# BBB_Headers.net
KiCad netlist of a schematic drawn in Altium Designer
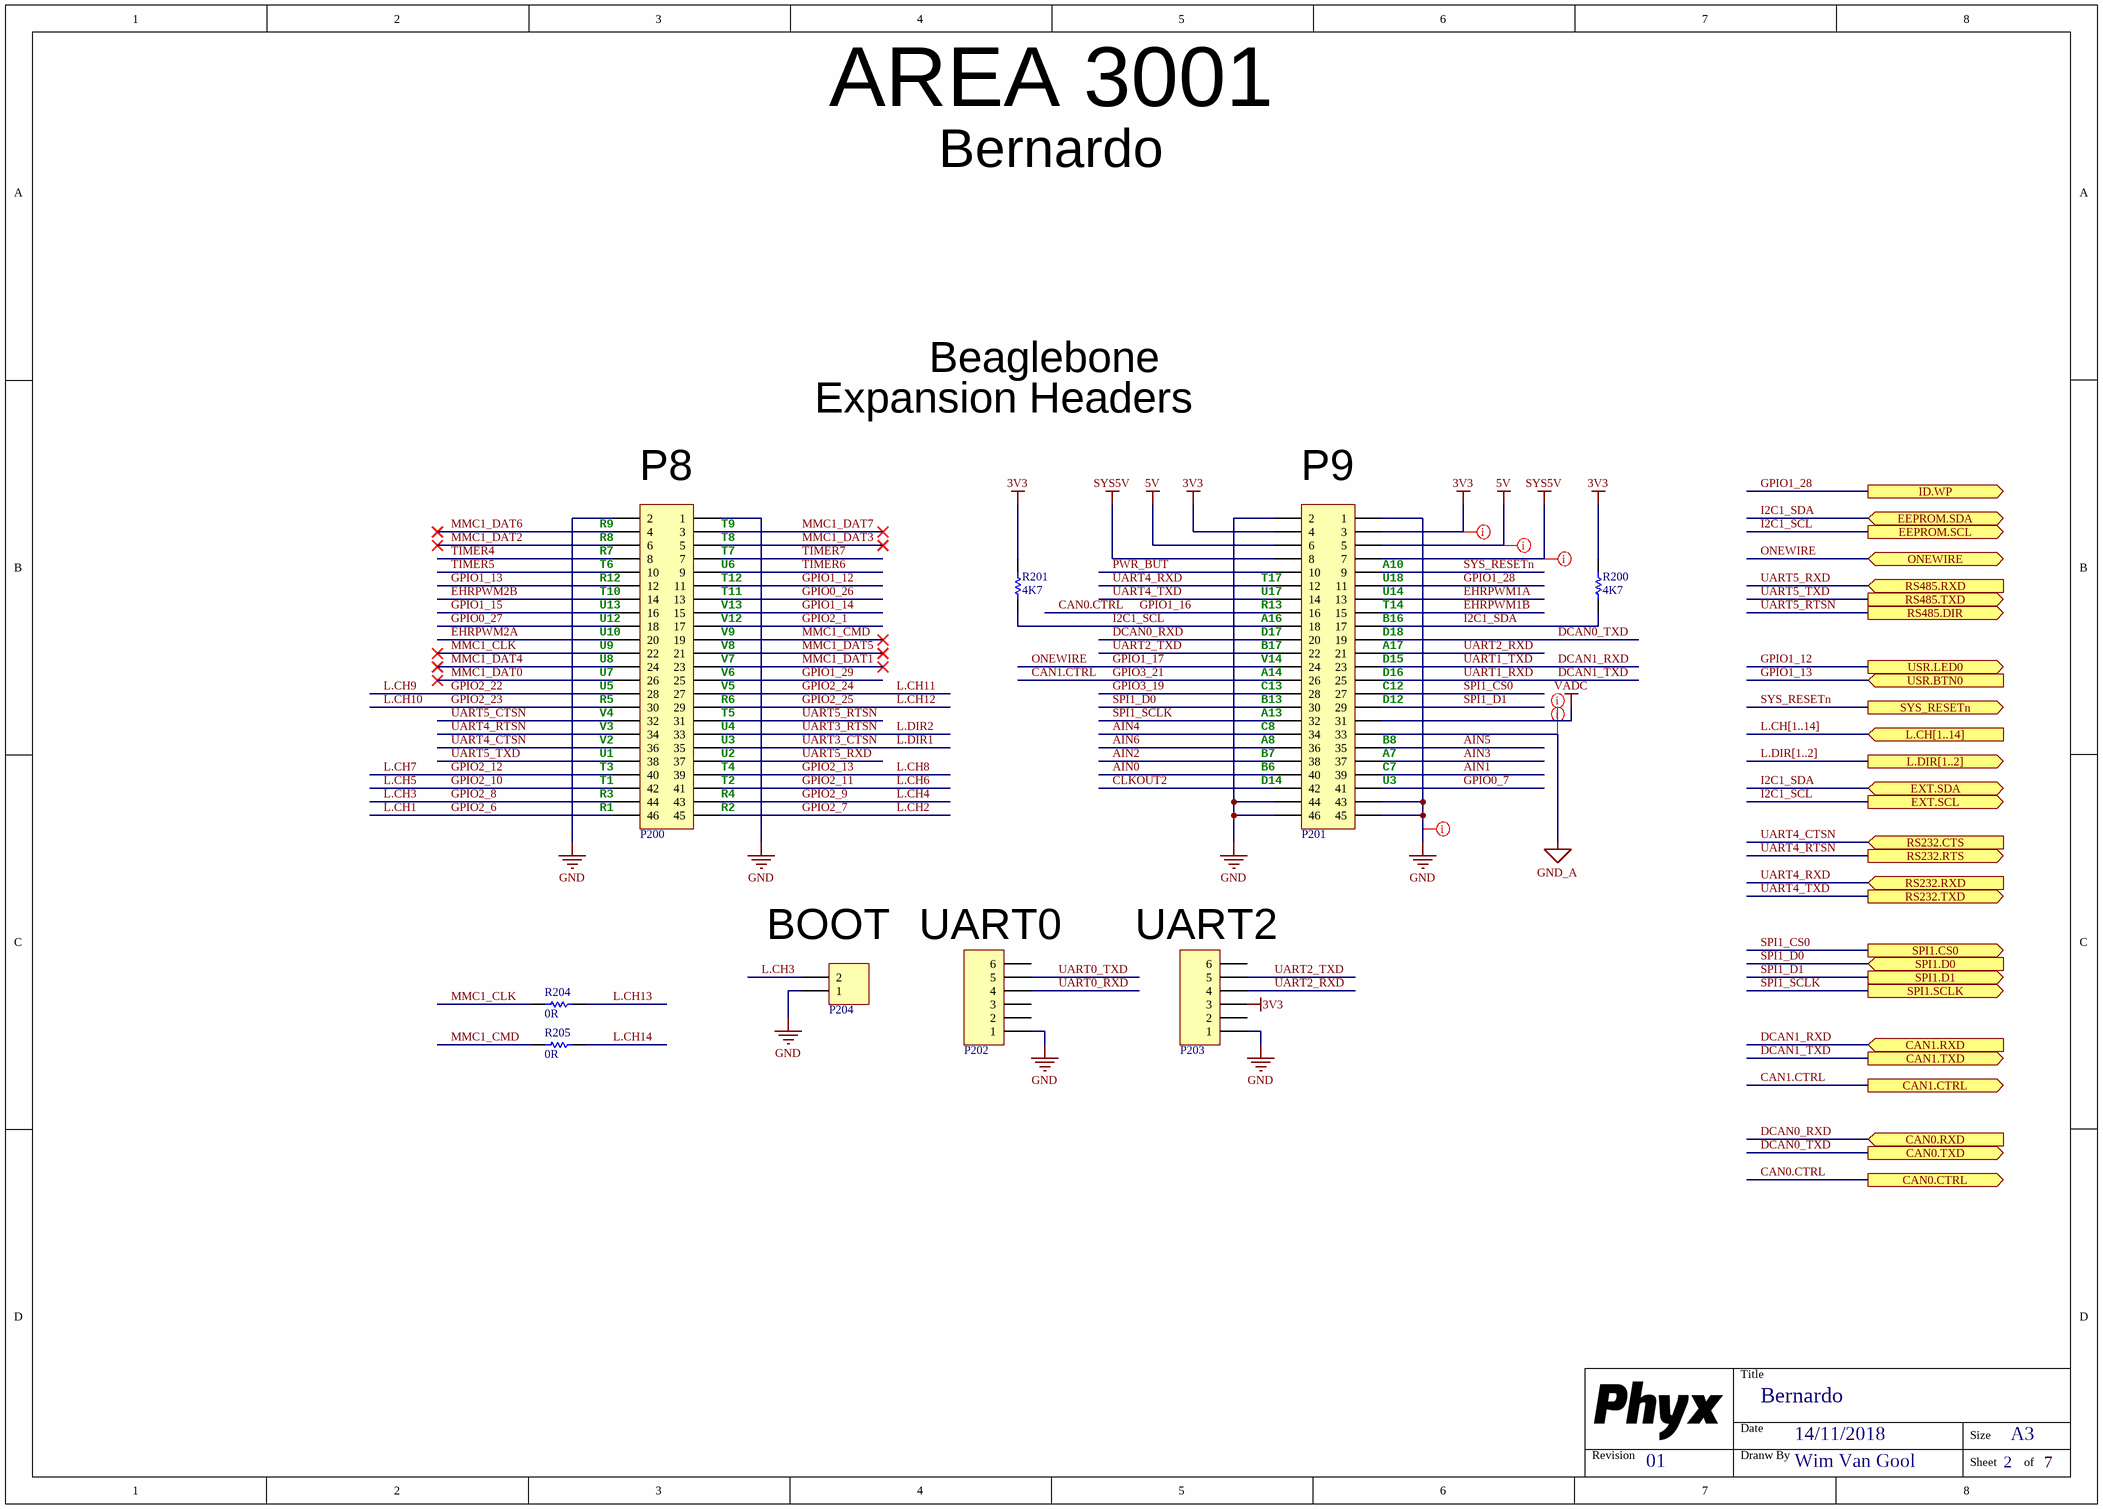
[diagram p0: BBB_Headers.SchDoc]

(export (version "E")
  (design (tool "Eeschema 10.0.6"))
  (components
    (comp (ref "P200")
      (value "Receptacle 23X2")
      (footprint "HDR2X23")
      (description "=Description")
      (libsource (lib "Phyx_Components") (part "Header 23X2"))
    )
    (comp (ref "P201")
      (value "Receptacle 23X2")
      (footprint "HDR2X23")
      (description "=Description")
      (libsource (lib "Phyx_Components") (part "Header 23X2"))
    )
    (comp (ref "P202")
      (value "Receptacle 6")
      (footprint "RCPT1X6")
      (libsource (lib "Phyx_Components") (part "Header 6"))
    )
    (comp (ref "P203")
      (value "Header 6")
      (footprint "HDR1X6")
      (libsource (lib "Phyx_Components") (part "Header 6"))
    )
    (comp (ref "P204")
      (value "Header 2")
      (footprint "HDR1X2")
      (libsource (lib "Phyx_Components") (part "Header 2"))
    )
    (comp (ref "R200")
      (value "4K7")
      (footprint "R0603_N")
      (fields (field (name "Comment") "RESISTOR"))
      (libsource (lib "Phyx_Components") (part "RESISTOR"))
    )
    (comp (ref "R201")
      (value "4K7")
      (footprint "R0603_N")
      (fields (field (name "Comment") "RESISTOR"))
      (libsource (lib "Phyx_Components") (part "RESISTOR"))
    )
    (comp (ref "R204")
      (value "0R")
      (footprint "R0603_N")
      (fields (field (name "Comment") "RESISTOR"))
      (libsource (lib "Phyx_Components") (part "RESISTOR"))
    )
    (comp (ref "R205")
      (value "0R")
      (footprint "R0603_N")
      (fields (field (name "Comment") "RESISTOR"))
      (libsource (lib "Phyx_Components") (part "RESISTOR"))
    )
  )
  (nets
    (net (code "2") (name "/AIN0") (class "Default")
      (node (ref "P201") (pin "40") (pinfunction "40_40") (pintype "passive"))
    )
    (net (code "3") (name "/AIN1") (class "Default")
      (node (ref "P201") (pin "39") (pinfunction "39_39") (pintype "passive"))
    )
    (net (code "4") (name "/AIN2") (class "Default")
      (node (ref "P201") (pin "38") (pinfunction "38_38") (pintype "passive"))
    )
    (net (code "5") (name "/AIN3") (class "Default")
      (node (ref "P201") (pin "37") (pinfunction "37_37") (pintype "passive"))
    )
    (net (code "6") (name "/AIN4") (class "Default")
      (node (ref "P201") (pin "34") (pinfunction "34_34") (pintype "passive"))
    )
    (net (code "7") (name "/AIN5") (class "Default")
      (node (ref "P201") (pin "35") (pinfunction "35_35") (pintype "passive"))
    )
    (net (code "8") (name "/AIN6") (class "Default")
      (node (ref "P201") (pin "36") (pinfunction "36_36") (pintype "passive"))
    )
    (net (code "9") (name "/CAN0.CTRL") (class "Default")
      (node (ref "P201") (pin "16") (pinfunction "16_16") (pintype "passive"))
    )
    (net (code "10") (name "/CAN1.CTRL") (class "Default")
      (node (ref "P201") (pin "26") (pinfunction "26_26") (pintype "passive"))
    )
    (net (code "11") (name "/CLKOUT2") (class "Default")
      (node (ref "P201") (pin "42") (pinfunction "42_42") (pintype "passive"))
    )
    (net (code "12") (name "/DCAN0_RXD") (class "Default")
      (node (ref "P201") (pin "20") (pinfunction "20_20") (pintype "passive"))
    )
    (net (code "13") (name "/DCAN0_TXD") (class "Default")
      (node (ref "P201") (pin "19") (pinfunction "19_19") (pintype "passive"))
    )
    (net (code "14") (name "/DCAN1_RXD") (class "Default")
      (node (ref "P201") (pin "23") (pinfunction "23_23") (pintype "passive"))
    )
    (net (code "15") (name "/DCAN1_TXD") (class "Default")
      (node (ref "P201") (pin "25") (pinfunction "25_25") (pintype "passive"))
    )
    (net (code "16") (name "/EHRPWM1A") (class "Default")
      (node (ref "P201") (pin "13") (pinfunction "13_13") (pintype "passive"))
    )
    (net (code "17") (name "/EHRPWM1B") (class "Default")
      (node (ref "P201") (pin "15") (pinfunction "15_15") (pintype "passive"))
    )
    (net (code "18") (name "/EHRPWM2A") (class "Default")
      (node (ref "P200") (pin "20") (pinfunction "20_20") (pintype "passive"))
    )
    (net (code "19") (name "/EHRPWM2B") (class "Default")
      (node (ref "P200") (pin "14") (pinfunction "14_14") (pintype "passive"))
    )
    (net (code "20") (name "/GPIO0_7") (class "Default")
      (node (ref "P201") (pin "41") (pinfunction "41_41") (pintype "passive"))
    )
    (net (code "21") (name "/GPIO0_26") (class "Default")
      (node (ref "P200") (pin "13") (pinfunction "13_13") (pintype "passive"))
    )
    (net (code "22") (name "/GPIO0_27") (class "Default")
      (node (ref "P200") (pin "18") (pinfunction "18_18") (pintype "passive"))
    )
    (net (code "23") (name "/GPIO1_12") (class "Default")
      (node (ref "P200") (pin "11") (pinfunction "11_11") (pintype "passive"))
    )
    (net (code "24") (name "/GPIO1_13") (class "Default")
      (node (ref "P200") (pin "12") (pinfunction "12_12") (pintype "passive"))
    )
    (net (code "25") (name "/GPIO1_14") (class "Default")
      (node (ref "P200") (pin "15") (pinfunction "15_15") (pintype "passive"))
    )
    (net (code "26") (name "/GPIO1_15") (class "Default")
      (node (ref "P200") (pin "16") (pinfunction "16_16") (pintype "passive"))
    )
    (net (code "27") (name "/GPIO1_17") (class "Default")
      (node (ref "P201") (pin "24") (pinfunction "24_24") (pintype "passive"))
    )
    (net (code "28") (name "/GPIO1_28") (class "Default")
      (node (ref "P201") (pin "11") (pinfunction "11_11") (pintype "passive"))
    )
    (net (code "29") (name "/GPIO1_29") (class "Default")
      (node (ref "P200") (pin "25") (pinfunction "25_25") (pintype "passive"))
    )
    (net (code "30") (name "/GPIO2_1") (class "Default")
      (node (ref "P200") (pin "17") (pinfunction "17_17") (pintype "passive"))
    )
    (net (code "31") (name "/GPIO3_19") (class "Default")
      (node (ref "P201") (pin "28") (pinfunction "28_28") (pintype "passive"))
    )
    (net (code "32") (name "/I2C1_SCL") (class "Default")
      (node (ref "P201") (pin "18") (pinfunction "18_18") (pintype "passive"))
      (node (ref "R201") (pin "1") (pinfunction "1_1") (pintype "passive"))
    )
    (net (code "33") (name "/I2C1_SDA") (class "Default")
      (node (ref "P201") (pin "17") (pinfunction "17_17") (pintype "passive"))
      (node (ref "R200") (pin "2") (pinfunction "2_2") (pintype "passive"))
    )
    (net (code "34") (name "/L.CH1") (class "Default")
      (node (ref "P200") (pin "46") (pinfunction "46_46") (pintype "passive"))
    )
    (net (code "35") (name "/L.CH2") (class "Default")
      (node (ref "P200") (pin "45") (pinfunction "45_45") (pintype "passive"))
    )
    (net (code "36") (name "/L.CH3") (class "Default")
      (node (ref "P200") (pin "44") (pinfunction "44_44") (pintype "passive"))
      (node (ref "P204") (pin "2") (pinfunction "2_2") (pintype "passive"))
    )
    (net (code "37") (name "/L.CH4") (class "Default")
      (node (ref "P200") (pin "43") (pinfunction "43_43") (pintype "passive"))
    )
    (net (code "38") (name "/L.CH5") (class "Default")
      (node (ref "P200") (pin "42") (pinfunction "42_42") (pintype "passive"))
    )
    (net (code "39") (name "/L.CH6") (class "Default")
      (node (ref "P200") (pin "41") (pinfunction "41_41") (pintype "passive"))
    )
    (net (code "40") (name "/L.CH7") (class "Default")
      (node (ref "P200") (pin "40") (pinfunction "40_40") (pintype "passive"))
    )
    (net (code "41") (name "/L.CH8") (class "Default")
      (node (ref "P200") (pin "39") (pinfunction "39_39") (pintype "passive"))
    )
    (net (code "42") (name "/L.CH9") (class "Default")
      (node (ref "P200") (pin "28") (pinfunction "28_28") (pintype "passive"))
    )
    (net (code "43") (name "/L.CH10") (class "Default")
      (node (ref "P200") (pin "30") (pinfunction "30_30") (pintype "passive"))
    )
    (net (code "44") (name "/L.CH11") (class "Default")
      (node (ref "P200") (pin "27") (pinfunction "27_27") (pintype "passive"))
    )
    (net (code "45") (name "/L.CH12") (class "Default")
      (node (ref "P200") (pin "29") (pinfunction "29_29") (pintype "passive"))
    )
    (net (code "46") (name "/L.CH13") (class "Default")
      (node (ref "R204") (pin "1") (pinfunction "1_1") (pintype "passive"))
    )
    (net (code "47") (name "/L.CH14") (class "Default")
      (node (ref "R205") (pin "1") (pinfunction "1_1") (pintype "passive"))
    )
    (net (code "49") (name "/L.DIR1") (class "Default")
      (node (ref "P200") (pin "35") (pinfunction "35_35") (pintype "passive"))
    )
    (net (code "50") (name "/L.DIR2") (class "Default")
      (node (ref "P200") (pin "33") (pinfunction "33_33") (pintype "passive"))
    )
    (net (code "52") (name "/MMC1_CLK") (class "Default")
      (node (ref "P200") (pin "22") (pinfunction "22_22") (pintype "passive"))
      (node (ref "R204") (pin "2") (pinfunction "2_2") (pintype "passive"))
    )
    (net (code "53") (name "/MMC1_CMD") (class "Default")
      (node (ref "P200") (pin "19") (pinfunction "19_19") (pintype "passive"))
      (node (ref "R205") (pin "2") (pinfunction "2_2") (pintype "passive"))
    )
    (net (code "54") (name "/MMC1_DAT0") (class "Default")
      (node (ref "P200") (pin "26") (pinfunction "26_26") (pintype "passive+no_connect"))
    )
    (net (code "55") (name "/MMC1_DAT1") (class "Default")
      (node (ref "P200") (pin "23") (pinfunction "23_23") (pintype "passive+no_connect"))
    )
    (net (code "56") (name "/MMC1_DAT2") (class "Default")
      (node (ref "P200") (pin "6") (pinfunction "6_6") (pintype "passive+no_connect"))
    )
    (net (code "57") (name "/MMC1_DAT3") (class "Default")
      (node (ref "P200") (pin "5") (pinfunction "5_5") (pintype "passive+no_connect"))
    )
    (net (code "58") (name "/MMC1_DAT4") (class "Default")
      (node (ref "P200") (pin "24") (pinfunction "24_24") (pintype "passive+no_connect"))
    )
    (net (code "59") (name "/MMC1_DAT5") (class "Default")
      (node (ref "P200") (pin "21") (pinfunction "21_21") (pintype "passive+no_connect"))
    )
    (net (code "60") (name "/MMC1_DAT6") (class "Default")
      (node (ref "P200") (pin "4") (pinfunction "4_4") (pintype "passive+no_connect"))
    )
    (net (code "61") (name "/MMC1_DAT7") (class "Default")
      (node (ref "P200") (pin "3") (pinfunction "3_3") (pintype "passive+no_connect"))
    )
    (net (code "62") (name "/PWR_BUT") (class "Default")
      (node (ref "P201") (pin "10") (pinfunction "10_10") (pintype "passive"))
    )
    (net (code "63") (name "/SPI1_CS0") (class "Default")
      (node (ref "P201") (pin "27") (pinfunction "27_27") (pintype "passive"))
    )
    (net (code "64") (name "/SPI1_D0") (class "Default")
      (node (ref "P201") (pin "30") (pinfunction "30_30") (pintype "passive"))
    )
    (net (code "65") (name "/SPI1_D1") (class "Default")
      (node (ref "P201") (pin "29") (pinfunction "29_29") (pintype "passive"))
    )
    (net (code "66") (name "/SPI1_SCLK") (class "Default")
      (node (ref "P201") (pin "32") (pinfunction "32_32") (pintype "passive"))
    )
    (net (code "67") (name "/SYS_RESETn") (class "Default")
      (node (ref "P201") (pin "9") (pinfunction "9_9") (pintype "passive"))
    )
    (net (code "68") (name "/TIMER4") (class "Default")
      (node (ref "P200") (pin "8") (pinfunction "8_8") (pintype "passive"))
    )
    (net (code "69") (name "/TIMER5") (class "Default")
      (node (ref "P200") (pin "10") (pinfunction "10_10") (pintype "passive"))
    )
    (net (code "70") (name "/TIMER6") (class "Default")
      (node (ref "P200") (pin "9") (pinfunction "9_9") (pintype "passive"))
    )
    (net (code "71") (name "/TIMER7") (class "Default")
      (node (ref "P200") (pin "7") (pinfunction "7_7") (pintype "passive"))
    )
    (net (code "72") (name "/UART0_RXD") (class "Default")
      (node (ref "P202") (pin "4") (pinfunction "4_4") (pintype "passive"))
    )
    (net (code "73") (name "/UART0_TXD") (class "Default")
      (node (ref "P202") (pin "5") (pinfunction "5_5") (pintype "passive"))
    )
    (net (code "74") (name "/UART2_RXD") (class "Default")
      (node (ref "P201") (pin "21") (pinfunction "21_21") (pintype "passive"))
      (node (ref "P203") (pin "4") (pinfunction "4_4") (pintype "passive"))
    )
    (net (code "75") (name "/UART2_TXD") (class "Default")
      (node (ref "P201") (pin "22") (pinfunction "22_22") (pintype "passive"))
      (node (ref "P203") (pin "5") (pinfunction "5_5") (pintype "passive"))
    )
    (net (code "76") (name "/UART4_CTSN") (class "Default")
      (node (ref "P200") (pin "36") (pinfunction "36_36") (pintype "passive"))
    )
    (net (code "77") (name "/UART4_RTSN") (class "Default")
      (node (ref "P200") (pin "34") (pinfunction "34_34") (pintype "passive"))
    )
    (net (code "78") (name "/UART4_RXD") (class "Default")
      (node (ref "P201") (pin "12") (pinfunction "12_12") (pintype "passive"))
    )
    (net (code "79") (name "/UART4_TXD") (class "Default")
      (node (ref "P201") (pin "14") (pinfunction "14_14") (pintype "passive"))
    )
    (net (code "80") (name "/UART5_CTSN") (class "Default")
      (node (ref "P200") (pin "32") (pinfunction "32_32") (pintype "passive"))
    )
    (net (code "81") (name "/UART5_RTSN") (class "Default")
      (node (ref "P200") (pin "31") (pinfunction "31_31") (pintype "passive"))
    )
    (net (code "82") (name "/UART5_RXD") (class "Default")
      (node (ref "P200") (pin "37") (pinfunction "37_37") (pintype "passive"))
    )
    (net (code "83") (name "/UART5_TXD") (class "Default")
      (node (ref "P200") (pin "38") (pinfunction "38_38") (pintype "passive"))
    )
    (net (code "84") (name "3V3") (class "Default")
      (node (ref "P201") (pin "3") (pinfunction "3_3") (pintype "passive"))
      (node (ref "P201") (pin "4") (pinfunction "4_4") (pintype "passive"))
      (node (ref "P203") (pin "3") (pinfunction "3_3") (pintype "passive"))
      (node (ref "R200") (pin "1") (pinfunction "1_1") (pintype "passive"))
      (node (ref "R201") (pin "2") (pinfunction "2_2") (pintype "passive"))
    )
    (net (code "85") (name "5V") (class "Default")
      (node (ref "P201") (pin "5") (pinfunction "5_5") (pintype "passive"))
      (node (ref "P201") (pin "6") (pinfunction "6_6") (pintype "passive"))
    )
    (net (code "86") (name "GND") (class "Default")
      (node (ref "P200") (pin "1") (pinfunction "1_1") (pintype "passive"))
      (node (ref "P200") (pin "2") (pinfunction "2_2") (pintype "passive"))
      (node (ref "P201") (pin "1") (pinfunction "1_1") (pintype "passive"))
      (node (ref "P201") (pin "2") (pinfunction "2_2") (pintype "passive"))
      (node (ref "P201") (pin "43") (pinfunction "43_43") (pintype "passive"))
      (node (ref "P201") (pin "44") (pinfunction "44_44") (pintype "passive"))
      (node (ref "P201") (pin "45") (pinfunction "45_45") (pintype "passive"))
      (node (ref "P201") (pin "46") (pinfunction "46_46") (pintype "passive"))
      (node (ref "P202") (pin "1") (pinfunction "1_1") (pintype "passive"))
      (node (ref "P203") (pin "1") (pinfunction "1_1") (pintype "passive"))
      (node (ref "P204") (pin "1") (pinfunction "1_1") (pintype "passive"))
    )
    (net (code "87") (name "GND_A") (class "Default")
      (node (ref "P201") (pin "33") (pinfunction "33_33") (pintype "passive"))
    )
    (net (code "88") (name "SYS5V") (class "Default")
      (node (ref "P201") (pin "7") (pinfunction "7_7") (pintype "passive"))
      (node (ref "P201") (pin "8") (pinfunction "8_8") (pintype "passive"))
    )
    (net (code "89") (name "VADC") (class "Default")
      (node (ref "P201") (pin "31") (pinfunction "31_31") (pintype "passive"))
    )
    (net (code "90") (name "unconnected-(P202-Pad2)") (class "Default")
      (node (ref "P202") (pin "2") (pinfunction "2_2") (pintype "passive"))
    )
    (net (code "91") (name "unconnected-(P202-Pad3)") (class "Default")
      (node (ref "P202") (pin "3") (pinfunction "3_3") (pintype "passive"))
    )
    (net (code "92") (name "unconnected-(P202-Pad6)") (class "Default")
      (node (ref "P202") (pin "6") (pinfunction "6_6") (pintype "passive"))
    )
    (net (code "93") (name "unconnected-(P203-Pad2)") (class "Default")
      (node (ref "P203") (pin "2") (pinfunction "2_2") (pintype "passive"))
    )
    (net (code "94") (name "unconnected-(P203-Pad6)") (class "Default")
      (node (ref "P203") (pin "6") (pinfunction "6_6") (pintype "passive"))
    )
  )
)
